# totem_pole_vcf.net
KiCad netlist of a schematic drawn in EAGLE
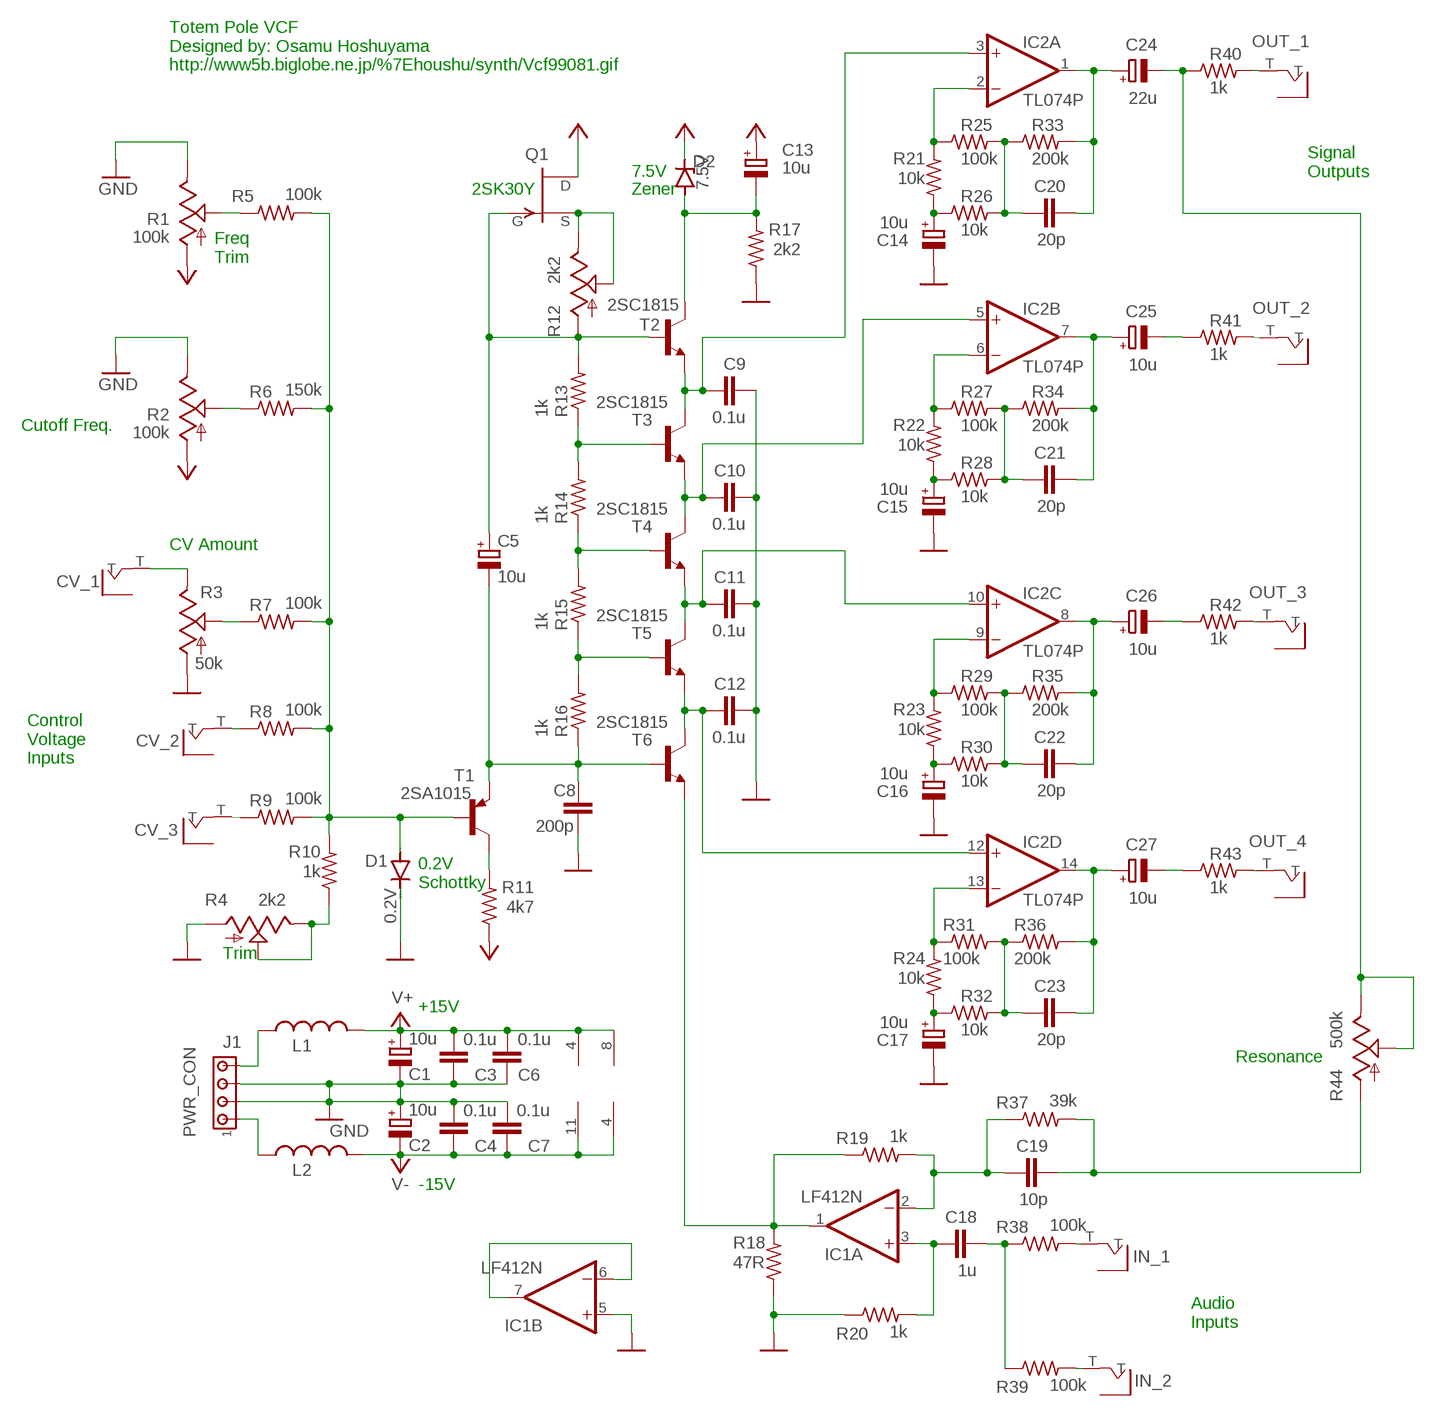
[diagram p0: schematic, sheet 1]

(export (version "E")
  (design (tool "Eeschema 10.0.6"))
  (components
    (comp (ref "C1")
      (value "10u")
      (footprint "eagle-import:E1,8-4")
      (libsource (lib "eagle-import") (part "CPOL-EUE1.8-4"))
    )
    (comp (ref "C2")
      (value "10u")
      (footprint "eagle-import:E1,8-4")
      (libsource (lib "eagle-import") (part "CPOL-EUE1.8-4"))
    )
    (comp (ref "C3")
      (value "0.1u")
      (footprint "eagle-import:C050-025X075")
      (libsource (lib "eagle-import") (part "C-EU050-025X075"))
    )
    (comp (ref "C4")
      (value "0.1u")
      (footprint "eagle-import:C050-025X075")
      (libsource (lib "eagle-import") (part "C-EU050-025X075"))
    )
    (comp (ref "C5")
      (value "10u")
      (footprint "eagle-import:E1,8-4")
      (libsource (lib "eagle-import") (part "CPOL-EUE1.8-4"))
    )
    (comp (ref "C6")
      (value "0.1u")
      (footprint "eagle-import:C050-025X075")
      (libsource (lib "eagle-import") (part "C-EU050-025X075"))
    )
    (comp (ref "C7")
      (value "0.1u")
      (footprint "eagle-import:C050-025X075")
      (libsource (lib "eagle-import") (part "C-EU050-025X075"))
    )
    (comp (ref "C8")
      (value "200p")
      (footprint "eagle-import:C050-025X075")
      (libsource (lib "eagle-import") (part "C-EU050-025X075"))
    )
    (comp (ref "C9")
      (value "0.1u")
      (footprint "eagle-import:C050-025X075")
      (libsource (lib "eagle-import") (part "C-EU050-025X075"))
    )
    (comp (ref "C10")
      (value "0.1u")
      (footprint "eagle-import:C050-025X075")
      (libsource (lib "eagle-import") (part "C-EU050-025X075"))
    )
    (comp (ref "C11")
      (value "0.1u")
      (footprint "eagle-import:C050-025X075")
      (libsource (lib "eagle-import") (part "C-EU050-025X075"))
    )
    (comp (ref "C12")
      (value "0.1u")
      (footprint "eagle-import:C050-025X075")
      (libsource (lib "eagle-import") (part "C-EU050-025X075"))
    )
    (comp (ref "C13")
      (value "10u")
      (footprint "eagle-import:E1,8-4")
      (libsource (lib "eagle-import") (part "CPOL-EUE1.8-4"))
    )
    (comp (ref "C14")
      (value "10u")
      (footprint "eagle-import:E1,8-4")
      (libsource (lib "eagle-import") (part "CPOL-EUE1.8-4"))
    )
    (comp (ref "C15")
      (value "10u")
      (footprint "eagle-import:E1,8-4")
      (libsource (lib "eagle-import") (part "CPOL-EUE1.8-4"))
    )
    (comp (ref "C16")
      (value "10u")
      (footprint "eagle-import:E1,8-4")
      (libsource (lib "eagle-import") (part "CPOL-EUE1.8-4"))
    )
    (comp (ref "C17")
      (value "10u")
      (footprint "eagle-import:E1,8-4")
      (libsource (lib "eagle-import") (part "CPOL-EUE1.8-4"))
    )
    (comp (ref "C18")
      (value "1u")
      (footprint "eagle-import:C050-025X075")
      (libsource (lib "eagle-import") (part "C-EU050-025X075"))
    )
    (comp (ref "C19")
      (value "10p")
      (footprint "eagle-import:C050-025X075")
      (libsource (lib "eagle-import") (part "C-EU050-025X075"))
    )
    (comp (ref "C20")
      (value "20p")
      (footprint "eagle-import:C050-025X075")
      (libsource (lib "eagle-import") (part "C-EU050-025X075"))
    )
    (comp (ref "C21")
      (value "20p")
      (footprint "eagle-import:C050-025X075")
      (libsource (lib "eagle-import") (part "C-EU050-025X075"))
    )
    (comp (ref "C22")
      (value "20p")
      (footprint "eagle-import:C050-025X075")
      (libsource (lib "eagle-import") (part "C-EU050-025X075"))
    )
    (comp (ref "C23")
      (value "20p")
      (footprint "eagle-import:C050-025X075")
      (libsource (lib "eagle-import") (part "C-EU050-025X075"))
    )
    (comp (ref "C24")
      (value "22u")
      (footprint "eagle-import:E1,8-4")
      (libsource (lib "eagle-import") (part "CPOL-EUE1.8-4"))
    )
    (comp (ref "C25")
      (value "10u")
      (footprint "eagle-import:E1,8-4")
      (libsource (lib "eagle-import") (part "CPOL-EUE1.8-4"))
    )
    (comp (ref "C26")
      (value "10u")
      (footprint "eagle-import:E1,8-4")
      (libsource (lib "eagle-import") (part "CPOL-EUE1.8-4"))
    )
    (comp (ref "C27")
      (value "10u")
      (footprint "eagle-import:E1,8-4")
      (libsource (lib "eagle-import") (part "CPOL-EUE1.8-4"))
    )
    (comp (ref "CV_1")
      (value "OFFBOARD_JACK")
      (footprint "eagle-import:OFFBOARD_JACK")
      (libsource (lib "eagle-import") (part "OFFBOARD_JACK"))
    )
    (comp (ref "CV_2")
      (value "OFFBOARD_JACK")
      (footprint "eagle-import:OFFBOARD_JACK")
      (libsource (lib "eagle-import") (part "OFFBOARD_JACK"))
    )
    (comp (ref "CV_3")
      (value "OFFBOARD_JACK")
      (footprint "eagle-import:OFFBOARD_JACK")
      (libsource (lib "eagle-import") (part "OFFBOARD_JACK"))
    )
    (comp (ref "D1")
      (value "0.2V")
      (footprint "eagle-import:D-10")
      (libsource (lib "eagle-import") (part "DIODE-D-10"))
    )
    (comp (ref "D2")
      (value "7.5V")
      (footprint "eagle-import:DO41Z10")
      (libsource (lib "eagle-import") (part "ZENER-DIODEDO41Z10"))
    )
    (comp (ref "IC1")
      (value "LF412N")
      (footprint "eagle-import:DIL08")
      (libsource (lib "eagle-import") (part "LF412N"))
    )
    (comp (ref "IC2")
      (value "TL074P")
      (footprint "eagle-import:DIL14")
      (libsource (lib "eagle-import") (part "TL074P"))
    )
    (comp (ref "IN_1")
      (value "OFFBOARD_JACK")
      (footprint "eagle-import:OFFBOARD_JACK")
      (libsource (lib "eagle-import") (part "OFFBOARD_JACK"))
    )
    (comp (ref "IN_2")
      (value "OFFBOARD_JACK")
      (footprint "eagle-import:OFFBOARD_JACK")
      (libsource (lib "eagle-import") (part "OFFBOARD_JACK"))
    )
    (comp (ref "J1")
      (value "PWR_CON")
      (footprint "eagle-import:1X4MTA")
      (libsource (lib "eagle-import") (part "MTA04-156"))
    )
    (comp (ref "L1")
      (value "BEAD")
      (footprint "eagle-import:0207_10")
      (libsource (lib "eagle-import") (part "L-US0207/10"))
    )
    (comp (ref "L2")
      (value "BEAD")
      (footprint "eagle-import:0207_10")
      (libsource (lib "eagle-import") (part "L-US0207/10"))
    )
    (comp (ref "OUT_1")
      (value "OFFBOARD_JACK")
      (footprint "eagle-import:OFFBOARD_JACK")
      (libsource (lib "eagle-import") (part "OFFBOARD_JACK"))
    )
    (comp (ref "OUT_2")
      (value "OFFBOARD_JACK")
      (footprint "eagle-import:OFFBOARD_JACK")
      (libsource (lib "eagle-import") (part "OFFBOARD_JACK"))
    )
    (comp (ref "OUT_3")
      (value "OFFBOARD_JACK")
      (footprint "eagle-import:OFFBOARD_JACK")
      (libsource (lib "eagle-import") (part "OFFBOARD_JACK"))
    )
    (comp (ref "OUT_4")
      (value "OFFBOARD_JACK")
      (footprint "eagle-import:OFFBOARD_JACK")
      (libsource (lib "eagle-import") (part "OFFBOARD_JACK"))
    )
    (comp (ref "Q1")
      (value "2N3819")
      (footprint "eagle-import:TO92")
      (libsource (lib "eagle-import") (part "2N3819"))
    )
    (comp (ref "R1")
      (value "100k")
      (footprint "eagle-import:RS3")
      (libsource (lib "eagle-import") (part "TRIM_US-RS3"))
    )
    (comp (ref "R2")
      (value "100k")
      (footprint "eagle-import:B64Y")
      (libsource (lib "eagle-import") (part "TRIM_US-B64Y"))
    )
    (comp (ref "R3")
      (value "50k")
      (footprint "eagle-import:B64Y")
      (libsource (lib "eagle-import") (part "TRIM_US-B64Y"))
    )
    (comp (ref "R4")
      (value "2k2")
      (footprint "eagle-import:RS3")
      (libsource (lib "eagle-import") (part "TRIM_US-RS3"))
    )
    (comp (ref "R5")
      (value "100k")
      (footprint "eagle-import:0207_10")
      (libsource (lib "eagle-import") (part "R-US_0207/10"))
    )
    (comp (ref "R6")
      (value "150k")
      (footprint "eagle-import:0207_10")
      (libsource (lib "eagle-import") (part "R-US_0207/10"))
    )
    (comp (ref "R7")
      (value "100k")
      (footprint "eagle-import:0207_10")
      (libsource (lib "eagle-import") (part "R-US_0207/10"))
    )
    (comp (ref "R8")
      (value "100k")
      (footprint "eagle-import:0207_10")
      (libsource (lib "eagle-import") (part "R-US_0207/10"))
    )
    (comp (ref "R9")
      (value "100k")
      (footprint "eagle-import:0207_10")
      (libsource (lib "eagle-import") (part "R-US_0207/10"))
    )
    (comp (ref "R10")
      (value "1k")
      (footprint "eagle-import:0207_10")
      (libsource (lib "eagle-import") (part "R-US_0207/10"))
    )
    (comp (ref "R11")
      (value "4k7")
      (footprint "eagle-import:0207_10")
      (libsource (lib "eagle-import") (part "R-US_0207/10"))
    )
    (comp (ref "R12")
      (value "2k2")
      (footprint "eagle-import:RS3")
      (libsource (lib "eagle-import") (part "TRIM_US-RS3"))
    )
    (comp (ref "R13")
      (value "1k")
      (footprint "eagle-import:0207_10")
      (libsource (lib "eagle-import") (part "R-US_0207/10"))
    )
    (comp (ref "R14")
      (value "1k")
      (footprint "eagle-import:0207_10")
      (libsource (lib "eagle-import") (part "R-US_0207/10"))
    )
    (comp (ref "R15")
      (value "1k")
      (footprint "eagle-import:0207_10")
      (libsource (lib "eagle-import") (part "R-US_0207/10"))
    )
    (comp (ref "R16")
      (value "1k")
      (footprint "eagle-import:0207_10")
      (libsource (lib "eagle-import") (part "R-US_0207/10"))
    )
    (comp (ref "R17")
      (value "2k2")
      (footprint "eagle-import:0207_10")
      (libsource (lib "eagle-import") (part "R-US_0207/10"))
    )
    (comp (ref "R18")
      (value "47R")
      (footprint "eagle-import:0207_10")
      (libsource (lib "eagle-import") (part "R-US_0207/10"))
    )
    (comp (ref "R19")
      (value "1k")
      (footprint "eagle-import:0207_10")
      (libsource (lib "eagle-import") (part "R-US_0207/10"))
    )
    (comp (ref "R20")
      (value "1k")
      (footprint "eagle-import:0207_10")
      (libsource (lib "eagle-import") (part "R-US_0207/10"))
    )
    (comp (ref "R21")
      (value "10k")
      (footprint "eagle-import:0207_10")
      (libsource (lib "eagle-import") (part "R-US_0207/10"))
    )
    (comp (ref "R22")
      (value "10k")
      (footprint "eagle-import:0207_10")
      (libsource (lib "eagle-import") (part "R-US_0207/10"))
    )
    (comp (ref "R23")
      (value "10k")
      (footprint "eagle-import:0207_10")
      (libsource (lib "eagle-import") (part "R-US_0207/10"))
    )
    (comp (ref "R24")
      (value "10k")
      (footprint "eagle-import:0207_10")
      (libsource (lib "eagle-import") (part "R-US_0207/10"))
    )
    (comp (ref "R25")
      (value "100k")
      (footprint "eagle-import:0207_10")
      (libsource (lib "eagle-import") (part "R-US_0207/10"))
    )
    (comp (ref "R26")
      (value "10k")
      (footprint "eagle-import:0207_10")
      (libsource (lib "eagle-import") (part "R-US_0207/10"))
    )
    (comp (ref "R27")
      (value "100k")
      (footprint "eagle-import:0207_10")
      (libsource (lib "eagle-import") (part "R-US_0207/10"))
    )
    (comp (ref "R28")
      (value "10k")
      (footprint "eagle-import:0207_10")
      (libsource (lib "eagle-import") (part "R-US_0207/10"))
    )
    (comp (ref "R29")
      (value "100k")
      (footprint "eagle-import:0207_10")
      (libsource (lib "eagle-import") (part "R-US_0207/10"))
    )
    (comp (ref "R30")
      (value "10k")
      (footprint "eagle-import:0207_10")
      (libsource (lib "eagle-import") (part "R-US_0207/10"))
    )
    (comp (ref "R31")
      (value "100k")
      (footprint "eagle-import:0207_10")
      (libsource (lib "eagle-import") (part "R-US_0207/10"))
    )
    (comp (ref "R32")
      (value "10k")
      (footprint "eagle-import:0207_10")
      (libsource (lib "eagle-import") (part "R-US_0207/10"))
    )
    (comp (ref "R33")
      (value "200k")
      (footprint "eagle-import:0207_10")
      (libsource (lib "eagle-import") (part "R-US_0207/10"))
    )
    (comp (ref "R34")
      (value "200k")
      (footprint "eagle-import:0207_10")
      (libsource (lib "eagle-import") (part "R-US_0207/10"))
    )
    (comp (ref "R35")
      (value "200k")
      (footprint "eagle-import:0207_10")
      (libsource (lib "eagle-import") (part "R-US_0207/10"))
    )
    (comp (ref "R36")
      (value "200k")
      (footprint "eagle-import:0207_10")
      (libsource (lib "eagle-import") (part "R-US_0207/10"))
    )
    (comp (ref "R37")
      (value "39k")
      (footprint "eagle-import:0207_10")
      (libsource (lib "eagle-import") (part "R-US_0207/10"))
    )
    (comp (ref "R38")
      (value "100k")
      (footprint "eagle-import:0207_10")
      (libsource (lib "eagle-import") (part "R-US_0207/10"))
    )
    (comp (ref "R39")
      (value "100k")
      (footprint "eagle-import:0207_10")
      (libsource (lib "eagle-import") (part "R-US_0207/10"))
    )
    (comp (ref "R40")
      (value "1k")
      (footprint "eagle-import:0207_10")
      (libsource (lib "eagle-import") (part "R-US_0207/10"))
    )
    (comp (ref "R41")
      (value "1k")
      (footprint "eagle-import:0207_10")
      (libsource (lib "eagle-import") (part "R-US_0207/10"))
    )
    (comp (ref "R42")
      (value "1k")
      (footprint "eagle-import:0207_10")
      (libsource (lib "eagle-import") (part "R-US_0207/10"))
    )
    (comp (ref "R43")
      (value "1k")
      (footprint "eagle-import:0207_10")
      (libsource (lib "eagle-import") (part "R-US_0207/10"))
    )
    (comp (ref "R44")
      (value "500k")
      (footprint "eagle-import:RS3")
      (libsource (lib "eagle-import") (part "TRIM_US-RS3"))
    )
    (comp (ref "T1")
      (value "2SA1015")
      (footprint "eagle-import:TO92")
      (libsource (lib "eagle-import") (part "-PNP-TO92"))
    )
    (comp (ref "T2")
      (value "2SC1815")
      (footprint "eagle-import:TO92-ECB")
      (libsource (lib "eagle-import") (part "2SC1815"))
    )
    (comp (ref "T3")
      (value "2SC1815")
      (footprint "eagle-import:TO92-ECB")
      (libsource (lib "eagle-import") (part "2SC1815"))
    )
    (comp (ref "T4")
      (value "2SC1815")
      (footprint "eagle-import:TO92-ECB")
      (libsource (lib "eagle-import") (part "2SC1815"))
    )
    (comp (ref "T5")
      (value "2SC1815")
      (footprint "eagle-import:TO92-ECB")
      (libsource (lib "eagle-import") (part "2SC1815"))
    )
    (comp (ref "T6")
      (value "2SC1815")
      (footprint "eagle-import:TO92-ECB")
      (libsource (lib "eagle-import") (part "2SC1815"))
    )
  )
  (nets
    (net (code "1") (name "GND") (class "Default")
      (node (ref "C1") (pin "-") (pinfunction "-_-") (pintype "passive"))
      (node (ref "C10") (pin "2") (pinfunction "2_2") (pintype "passive"))
      (node (ref "C11") (pin "2") (pinfunction "2_2") (pintype "passive"))
      (node (ref "C12") (pin "2") (pinfunction "2_2") (pintype "passive"))
      (node (ref "C14") (pin "-") (pinfunction "-_-") (pintype "passive"))
      (node (ref "C15") (pin "-") (pinfunction "-_-") (pintype "passive"))
      (node (ref "C16") (pin "-") (pinfunction "-_-") (pintype "passive"))
      (node (ref "C17") (pin "-") (pinfunction "-_-") (pintype "passive"))
      (node (ref "C2") (pin "+") (pinfunction "+_+") (pintype "passive"))
      (node (ref "C3") (pin "2") (pinfunction "2_2") (pintype "passive"))
      (node (ref "C4") (pin "1") (pinfunction "1_1") (pintype "passive"))
      (node (ref "C6") (pin "1") (pinfunction "1_1") (pintype "passive"))
      (node (ref "C7") (pin "1") (pinfunction "1_1") (pintype "passive"))
      (node (ref "C8") (pin "1") (pinfunction "1_1") (pintype "passive"))
      (node (ref "C9") (pin "2") (pinfunction "2_2") (pintype "passive"))
      (node (ref "D1") (pin "C") (pinfunction "C_C") (pintype "passive"))
      (node (ref "IC1") (pin "5") (pinfunction "+IN_5") (pintype "input"))
      (node (ref "J1") (pin "2") (pinfunction "2_2") (pintype "passive"))
      (node (ref "J1") (pin "3") (pinfunction "3_3") (pintype "passive"))
      (node (ref "R1") (pin "E") (pinfunction "E_E") (pintype "passive"))
      (node (ref "R17") (pin "1") (pinfunction "1_1") (pintype "passive"))
      (node (ref "R18") (pin "1") (pinfunction "1_1") (pintype "passive"))
      (node (ref "R2") (pin "E") (pinfunction "E_E") (pintype "passive"))
      (node (ref "R20") (pin "1") (pinfunction "1_1") (pintype "passive"))
      (node (ref "R3") (pin "A") (pinfunction "A_A") (pintype "passive"))
      (node (ref "R4") (pin "A") (pinfunction "A_A") (pintype "passive"))
    )
    (net (code "2") (name "Net-(C13-Pad-)") (class "Default")
      (node (ref "C13") (pin "-") (pinfunction "-_-") (pintype "passive"))
      (node (ref "D2") (pin "A") (pinfunction "A_A") (pintype "passive"))
      (node (ref "R17") (pin "2") (pinfunction "2_2") (pintype "passive"))
      (node (ref "T2") (pin "C") (pinfunction "C_C") (pintype "passive"))
    )
    (net (code "3") (name "Net-(C14-Pad+)") (class "Default")
      (node (ref "C14") (pin "+") (pinfunction "+_+") (pintype "passive"))
      (node (ref "R21") (pin "1") (pinfunction "1_1") (pintype "passive"))
      (node (ref "R26") (pin "1") (pinfunction "1_1") (pintype "passive"))
    )
    (net (code "4") (name "Net-(C15-Pad+)") (class "Default")
      (node (ref "C15") (pin "+") (pinfunction "+_+") (pintype "passive"))
      (node (ref "R22") (pin "1") (pinfunction "1_1") (pintype "passive"))
      (node (ref "R28") (pin "1") (pinfunction "1_1") (pintype "passive"))
    )
    (net (code "5") (name "Net-(C16-Pad+)") (class "Default")
      (node (ref "C16") (pin "+") (pinfunction "+_+") (pintype "passive"))
      (node (ref "R23") (pin "1") (pinfunction "1_1") (pintype "passive"))
      (node (ref "R30") (pin "1") (pinfunction "1_1") (pintype "passive"))
    )
    (net (code "6") (name "Net-(C17-Pad+)") (class "Default")
      (node (ref "C17") (pin "+") (pinfunction "+_+") (pintype "passive"))
      (node (ref "R24") (pin "1") (pinfunction "1_1") (pintype "passive"))
      (node (ref "R32") (pin "1") (pinfunction "1_1") (pintype "passive"))
    )
    (net (code "7") (name "Net-(C18-Pad2)") (class "Default")
      (node (ref "C18") (pin "2") (pinfunction "2_2") (pintype "passive"))
      (node (ref "R38") (pin "1") (pinfunction "1_1") (pintype "passive"))
      (node (ref "R39") (pin "1") (pinfunction "1_1") (pintype "passive"))
    )
    (net (code "8") (name "Net-(C19-Pad2)") (class "Default")
      (node (ref "C19") (pin "2") (pinfunction "2_2") (pintype "passive"))
      (node (ref "R37") (pin "2") (pinfunction "2_2") (pintype "passive"))
      (node (ref "R44") (pin "A") (pinfunction "A_A") (pintype "passive"))
    )
    (net (code "9") (name "Net-(C20-Pad1)") (class "Default")
      (node (ref "C20") (pin "1") (pinfunction "1_1") (pintype "passive"))
      (node (ref "R25") (pin "2") (pinfunction "2_2") (pintype "passive"))
      (node (ref "R26") (pin "2") (pinfunction "2_2") (pintype "passive"))
      (node (ref "R33") (pin "1") (pinfunction "1_1") (pintype "passive"))
    )
    (net (code "10") (name "Net-(C21-Pad1)") (class "Default")
      (node (ref "C21") (pin "1") (pinfunction "1_1") (pintype "passive"))
      (node (ref "R27") (pin "2") (pinfunction "2_2") (pintype "passive"))
      (node (ref "R28") (pin "2") (pinfunction "2_2") (pintype "passive"))
      (node (ref "R34") (pin "1") (pinfunction "1_1") (pintype "passive"))
    )
    (net (code "11") (name "Net-(C22-Pad1)") (class "Default")
      (node (ref "C22") (pin "1") (pinfunction "1_1") (pintype "passive"))
      (node (ref "R29") (pin "2") (pinfunction "2_2") (pintype "passive"))
      (node (ref "R30") (pin "2") (pinfunction "2_2") (pintype "passive"))
      (node (ref "R35") (pin "1") (pinfunction "1_1") (pintype "passive"))
    )
    (net (code "12") (name "Net-(C23-Pad1)") (class "Default")
      (node (ref "C23") (pin "1") (pinfunction "1_1") (pintype "passive"))
      (node (ref "R31") (pin "2") (pinfunction "2_2") (pintype "passive"))
      (node (ref "R32") (pin "2") (pinfunction "2_2") (pintype "passive"))
      (node (ref "R36") (pin "1") (pinfunction "1_1") (pintype "passive"))
    )
    (net (code "13") (name "Net-(C24-Pad-)") (class "Default")
      (node (ref "C24") (pin "-") (pinfunction "-_-") (pintype "passive"))
      (node (ref "R40") (pin "1") (pinfunction "1_1") (pintype "passive"))
      (node (ref "R44") (pin "E") (pinfunction "E_E") (pintype "passive"))
      (node (ref "R44") (pin "S") (pinfunction "S_S") (pintype "passive"))
    )
    (net (code "14") (name "Net-(C25-Pad-)") (class "Default")
      (node (ref "C25") (pin "-") (pinfunction "-_-") (pintype "passive"))
      (node (ref "R41") (pin "1") (pinfunction "1_1") (pintype "passive"))
    )
    (net (code "15") (name "Net-(C26-Pad-)") (class "Default")
      (node (ref "C26") (pin "-") (pinfunction "-_-") (pintype "passive"))
      (node (ref "R42") (pin "1") (pinfunction "1_1") (pintype "passive"))
    )
    (net (code "16") (name "Net-(C27-Pad-)") (class "Default")
      (node (ref "C27") (pin "-") (pinfunction "-_-") (pintype "passive"))
      (node (ref "R43") (pin "1") (pinfunction "1_1") (pintype "passive"))
    )
    (net (code "17") (name "Net-(CV_1-PadT)") (class "Default")
      (node (ref "CV_1") (pin "T") (pinfunction "T_T") (pintype "bidirectional"))
      (node (ref "R3") (pin "E") (pinfunction "E_E") (pintype "passive"))
    )
    (net (code "18") (name "Net-(CV_2-PadT)") (class "Default")
      (node (ref "CV_2") (pin "T") (pinfunction "T_T") (pintype "bidirectional"))
      (node (ref "R8") (pin "1") (pinfunction "1_1") (pintype "passive"))
    )
    (net (code "19") (name "Net-(CV_3-PadT)") (class "Default")
      (node (ref "CV_3") (pin "T") (pinfunction "T_T") (pintype "bidirectional"))
      (node (ref "R9") (pin "1") (pinfunction "1_1") (pintype "passive"))
    )
    (net (code "20") (name "Net-(IC1A-+IN)") (class "Default")
      (node (ref "C18") (pin "1") (pinfunction "1_1") (pintype "passive"))
      (node (ref "IC1") (pin "3") (pinfunction "+IN_3") (pintype "input"))
      (node (ref "R20") (pin "2") (pinfunction "2_2") (pintype "passive"))
    )
    (net (code "21") (name "Net-(IC1A--IN)") (class "Default")
      (node (ref "C19") (pin "1") (pinfunction "1_1") (pintype "passive"))
      (node (ref "IC1") (pin "2") (pinfunction "-IN_2") (pintype "input"))
      (node (ref "R19") (pin "2") (pinfunction "2_2") (pintype "passive"))
      (node (ref "R37") (pin "1") (pinfunction "1_1") (pintype "passive"))
    )
    (net (code "22") (name "Net-(IC1A-OUT)") (class "Default")
      (node (ref "IC1") (pin "1") (pinfunction "OUT_1") (pintype "output"))
      (node (ref "R18") (pin "2") (pinfunction "2_2") (pintype "passive"))
      (node (ref "R19") (pin "1") (pinfunction "1_1") (pintype "passive"))
      (node (ref "T6") (pin "E") (pinfunction "E_E") (pintype "passive"))
    )
    (net (code "23") (name "Net-(IC1B--IN)") (class "Default")
      (node (ref "IC1") (pin "6") (pinfunction "-IN_6") (pintype "input"))
      (node (ref "IC1") (pin "7") (pinfunction "OUT_7") (pintype "output"))
    )
    (net (code "24") (name "Net-(IC2A-+IN)") (class "Default")
      (node (ref "C9") (pin "1") (pinfunction "1_1") (pintype "passive"))
      (node (ref "IC2") (pin "3") (pinfunction "+IN_3") (pintype "input"))
      (node (ref "T2") (pin "E") (pinfunction "E_E") (pintype "passive"))
      (node (ref "T3") (pin "C") (pinfunction "C_C") (pintype "passive"))
    )
    (net (code "25") (name "Net-(IC2A--IN)") (class "Default")
      (node (ref "IC2") (pin "2") (pinfunction "-IN_2") (pintype "input"))
      (node (ref "R21") (pin "2") (pinfunction "2_2") (pintype "passive"))
      (node (ref "R25") (pin "1") (pinfunction "1_1") (pintype "passive"))
    )
    (net (code "26") (name "Net-(IC2A-OUT)") (class "Default")
      (node (ref "C20") (pin "2") (pinfunction "2_2") (pintype "passive"))
      (node (ref "C24") (pin "+") (pinfunction "+_+") (pintype "passive"))
      (node (ref "IC2") (pin "1") (pinfunction "OUT_1") (pintype "output"))
      (node (ref "R33") (pin "2") (pinfunction "2_2") (pintype "passive"))
    )
    (net (code "27") (name "Net-(IC2B-+IN)") (class "Default")
      (node (ref "C10") (pin "1") (pinfunction "1_1") (pintype "passive"))
      (node (ref "IC2") (pin "5") (pinfunction "+IN_5") (pintype "input"))
      (node (ref "T3") (pin "E") (pinfunction "E_E") (pintype "passive"))
      (node (ref "T4") (pin "C") (pinfunction "C_C") (pintype "passive"))
    )
    (net (code "28") (name "Net-(IC2B--IN)") (class "Default")
      (node (ref "IC2") (pin "6") (pinfunction "-IN_6") (pintype "input"))
      (node (ref "R22") (pin "2") (pinfunction "2_2") (pintype "passive"))
      (node (ref "R27") (pin "1") (pinfunction "1_1") (pintype "passive"))
    )
    (net (code "29") (name "Net-(IC2B-OUT)") (class "Default")
      (node (ref "C21") (pin "2") (pinfunction "2_2") (pintype "passive"))
      (node (ref "C25") (pin "+") (pinfunction "+_+") (pintype "passive"))
      (node (ref "IC2") (pin "7") (pinfunction "OUT_7") (pintype "output"))
      (node (ref "R34") (pin "2") (pinfunction "2_2") (pintype "passive"))
    )
    (net (code "30") (name "Net-(IC2C-+IN)") (class "Default")
      (node (ref "C11") (pin "1") (pinfunction "1_1") (pintype "passive"))
      (node (ref "IC2") (pin "10") (pinfunction "+IN_10") (pintype "input"))
      (node (ref "T4") (pin "E") (pinfunction "E_E") (pintype "passive"))
      (node (ref "T5") (pin "C") (pinfunction "C_C") (pintype "passive"))
    )
    (net (code "31") (name "Net-(IC2C--IN)") (class "Default")
      (node (ref "IC2") (pin "9") (pinfunction "-IN_9") (pintype "input"))
      (node (ref "R23") (pin "2") (pinfunction "2_2") (pintype "passive"))
      (node (ref "R29") (pin "1") (pinfunction "1_1") (pintype "passive"))
    )
    (net (code "32") (name "Net-(IC2C-OUT)") (class "Default")
      (node (ref "C22") (pin "2") (pinfunction "2_2") (pintype "passive"))
      (node (ref "C26") (pin "+") (pinfunction "+_+") (pintype "passive"))
      (node (ref "IC2") (pin "8") (pinfunction "OUT_8") (pintype "output"))
      (node (ref "R35") (pin "2") (pinfunction "2_2") (pintype "passive"))
    )
    (net (code "33") (name "Net-(IC2D-+IN)") (class "Default")
      (node (ref "C12") (pin "1") (pinfunction "1_1") (pintype "passive"))
      (node (ref "IC2") (pin "12") (pinfunction "+IN_12") (pintype "input"))
      (node (ref "T5") (pin "E") (pinfunction "E_E") (pintype "passive"))
      (node (ref "T6") (pin "C") (pinfunction "C_C") (pintype "passive"))
    )
    (net (code "34") (name "Net-(IC2D--IN)") (class "Default")
      (node (ref "IC2") (pin "13") (pinfunction "-IN_13") (pintype "input"))
      (node (ref "R24") (pin "2") (pinfunction "2_2") (pintype "passive"))
      (node (ref "R31") (pin "1") (pinfunction "1_1") (pintype "passive"))
    )
    (net (code "35") (name "Net-(IC2D-OUT)") (class "Default")
      (node (ref "C23") (pin "2") (pinfunction "2_2") (pintype "passive"))
      (node (ref "C27") (pin "+") (pinfunction "+_+") (pintype "passive"))
      (node (ref "IC2") (pin "14") (pinfunction "OUT_14") (pintype "output"))
      (node (ref "R36") (pin "2") (pinfunction "2_2") (pintype "passive"))
    )
    (net (code "36") (name "Net-(IN_1-PadT)") (class "Default")
      (node (ref "IN_1") (pin "T") (pinfunction "T_T") (pintype "bidirectional"))
      (node (ref "R38") (pin "2") (pinfunction "2_2") (pintype "passive"))
    )
    (net (code "37") (name "Net-(IN_2-PadT)") (class "Default")
      (node (ref "IN_2") (pin "T") (pinfunction "T_T") (pintype "bidirectional"))
      (node (ref "R39") (pin "2") (pinfunction "2_2") (pintype "passive"))
    )
    (net (code "38") (name "Net-(J1-Pad1)") (class "Default")
      (node (ref "J1") (pin "1") (pinfunction "1_1") (pintype "passive"))
      (node (ref "L2") (pin "1") (pinfunction "1_1") (pintype "passive"))
    )
    (net (code "39") (name "Net-(J1-Pad4)") (class "Default")
      (node (ref "J1") (pin "4") (pinfunction "4_4") (pintype "passive"))
      (node (ref "L1") (pin "1") (pinfunction "1_1") (pintype "passive"))
    )
    (net (code "40") (name "Net-(OUT_1-PadT)") (class "Default")
      (node (ref "OUT_1") (pin "T") (pinfunction "T_T") (pintype "bidirectional"))
      (node (ref "R40") (pin "2") (pinfunction "2_2") (pintype "passive"))
    )
    (net (code "41") (name "Net-(OUT_2-PadT)") (class "Default")
      (node (ref "OUT_2") (pin "T") (pinfunction "T_T") (pintype "bidirectional"))
      (node (ref "R41") (pin "2") (pinfunction "2_2") (pintype "passive"))
    )
    (net (code "42") (name "Net-(OUT_3-PadT)") (class "Default")
      (node (ref "OUT_3") (pin "T") (pinfunction "T_T") (pintype "bidirectional"))
      (node (ref "R42") (pin "2") (pinfunction "2_2") (pintype "passive"))
    )
    (net (code "43") (name "Net-(OUT_4-PadT)") (class "Default")
      (node (ref "OUT_4") (pin "T") (pinfunction "T_T") (pintype "bidirectional"))
      (node (ref "R43") (pin "2") (pinfunction "2_2") (pintype "passive"))
    )
    (net (code "44") (name "Net-(Q1-G)") (class "Default")
      (node (ref "C5") (pin "+") (pinfunction "+_+") (pintype "passive"))
      (node (ref "Q1") (pin "2") (pinfunction "G_2") (pintype "passive"))
      (node (ref "R12") (pin "A") (pinfunction "A_A") (pintype "passive"))
      (node (ref "R13") (pin "2") (pinfunction "2_2") (pintype "passive"))
      (node (ref "T2") (pin "B") (pinfunction "B_B") (pintype "passive"))
    )
    (net (code "45") (name "Net-(Q1-S)") (class "Default")
      (node (ref "Q1") (pin "3") (pinfunction "S_3") (pintype "passive"))
      (node (ref "R12") (pin "E") (pinfunction "E_E") (pintype "passive"))
      (node (ref "R12") (pin "S") (pinfunction "S_S") (pintype "passive"))
    )
    (net (code "46") (name "Net-(R1-PadS)") (class "Default")
      (node (ref "R1") (pin "S") (pinfunction "S_S") (pintype "passive"))
      (node (ref "R5") (pin "1") (pinfunction "1_1") (pintype "passive"))
    )
    (net (code "47") (name "Net-(R2-PadS)") (class "Default")
      (node (ref "R2") (pin "S") (pinfunction "S_S") (pintype "passive"))
      (node (ref "R6") (pin "1") (pinfunction "1_1") (pintype "passive"))
    )
    (net (code "48") (name "Net-(R3-PadS)") (class "Default")
      (node (ref "R3") (pin "S") (pinfunction "S_S") (pintype "passive"))
      (node (ref "R7") (pin "1") (pinfunction "1_1") (pintype "passive"))
    )
    (net (code "49") (name "Net-(R10-Pad1)") (class "Default")
      (node (ref "R10") (pin "1") (pinfunction "1_1") (pintype "passive"))
      (node (ref "R4") (pin "E") (pinfunction "E_E") (pintype "passive"))
      (node (ref "R4") (pin "S") (pinfunction "S_S") (pintype "passive"))
    )
    (net (code "50") (name "Net-(R13-Pad1)") (class "Default")
      (node (ref "R13") (pin "1") (pinfunction "1_1") (pintype "passive"))
      (node (ref "R14") (pin "2") (pinfunction "2_2") (pintype "passive"))
      (node (ref "T3") (pin "B") (pinfunction "B_B") (pintype "passive"))
    )
    (net (code "51") (name "Net-(R14-Pad1)") (class "Default")
      (node (ref "R14") (pin "1") (pinfunction "1_1") (pintype "passive"))
      (node (ref "R15") (pin "2") (pinfunction "2_2") (pintype "passive"))
      (node (ref "T4") (pin "B") (pinfunction "B_B") (pintype "passive"))
    )
    (net (code "52") (name "Net-(R15-Pad1)") (class "Default")
      (node (ref "R15") (pin "1") (pinfunction "1_1") (pintype "passive"))
      (node (ref "R16") (pin "2") (pinfunction "2_2") (pintype "passive"))
      (node (ref "T5") (pin "B") (pinfunction "B_B") (pintype "passive"))
    )
    (net (code "53") (name "Net-(T1-B)") (class "Default")
      (node (ref "D1") (pin "A") (pinfunction "A_A") (pintype "passive"))
      (node (ref "R10") (pin "2") (pinfunction "2_2") (pintype "passive"))
      (node (ref "R5") (pin "2") (pinfunction "2_2") (pintype "passive"))
      (node (ref "R6") (pin "2") (pinfunction "2_2") (pintype "passive"))
      (node (ref "R7") (pin "2") (pinfunction "2_2") (pintype "passive"))
      (node (ref "R8") (pin "2") (pinfunction "2_2") (pintype "passive"))
      (node (ref "R9") (pin "2") (pinfunction "2_2") (pintype "passive"))
      (node (ref "T1") (pin "2") (pinfunction "B_2") (pintype "passive"))
    )
    (net (code "54") (name "Net-(T1-C)") (class "Default")
      (node (ref "R11") (pin "2") (pinfunction "2_2") (pintype "passive"))
      (node (ref "T1") (pin "3") (pinfunction "C_3") (pintype "passive"))
    )
    (net (code "55") (name "Net-(T1-E)") (class "Default")
      (node (ref "C5") (pin "-") (pinfunction "-_-") (pintype "passive"))
      (node (ref "C8") (pin "2") (pinfunction "2_2") (pintype "passive"))
      (node (ref "R16") (pin "1") (pinfunction "1_1") (pintype "passive"))
      (node (ref "T1") (pin "1") (pinfunction "E_1") (pintype "passive"))
      (node (ref "T6") (pin "B") (pinfunction "B_B") (pintype "passive"))
    )
    (net (code "56") (name "V+") (class "Default")
      (node (ref "C1") (pin "+") (pinfunction "+_+") (pintype "passive"))
      (node (ref "C13") (pin "+") (pinfunction "+_+") (pintype "passive"))
      (node (ref "C3") (pin "1") (pinfunction "1_1") (pintype "passive"))
      (node (ref "C6") (pin "2") (pinfunction "2_2") (pintype "passive"))
      (node (ref "D2") (pin "C") (pinfunction "C_C") (pintype "passive"))
      (node (ref "IC1") (pin "8") (pinfunction "V+_8") (pintype "power_in"))
      (node (ref "IC2") (pin "4") (pinfunction "V+_4") (pintype "power_in"))
      (node (ref "L1") (pin "2") (pinfunction "2_2") (pintype "passive"))
      (node (ref "Q1") (pin "1") (pinfunction "D_1") (pintype "passive"))
    )
    (net (code "57") (name "V-") (class "Default")
      (node (ref "C2") (pin "-") (pinfunction "-_-") (pintype "passive"))
      (node (ref "C4") (pin "2") (pinfunction "2_2") (pintype "passive"))
      (node (ref "C7") (pin "2") (pinfunction "2_2") (pintype "passive"))
      (node (ref "IC1") (pin "4") (pinfunction "V-_4") (pintype "power_in"))
      (node (ref "IC2") (pin "11") (pinfunction "V-_11") (pintype "power_in"))
      (node (ref "L2") (pin "2") (pinfunction "2_2") (pintype "passive"))
      (node (ref "R1") (pin "A") (pinfunction "A_A") (pintype "passive"))
      (node (ref "R11") (pin "1") (pinfunction "1_1") (pintype "passive"))
      (node (ref "R2") (pin "A") (pinfunction "A_A") (pintype "passive"))
    )
  )
)
